# SCH_PCBProjectCard_2024-06-02.net
KiCad netlist of a schematic drawn in EasyEDA
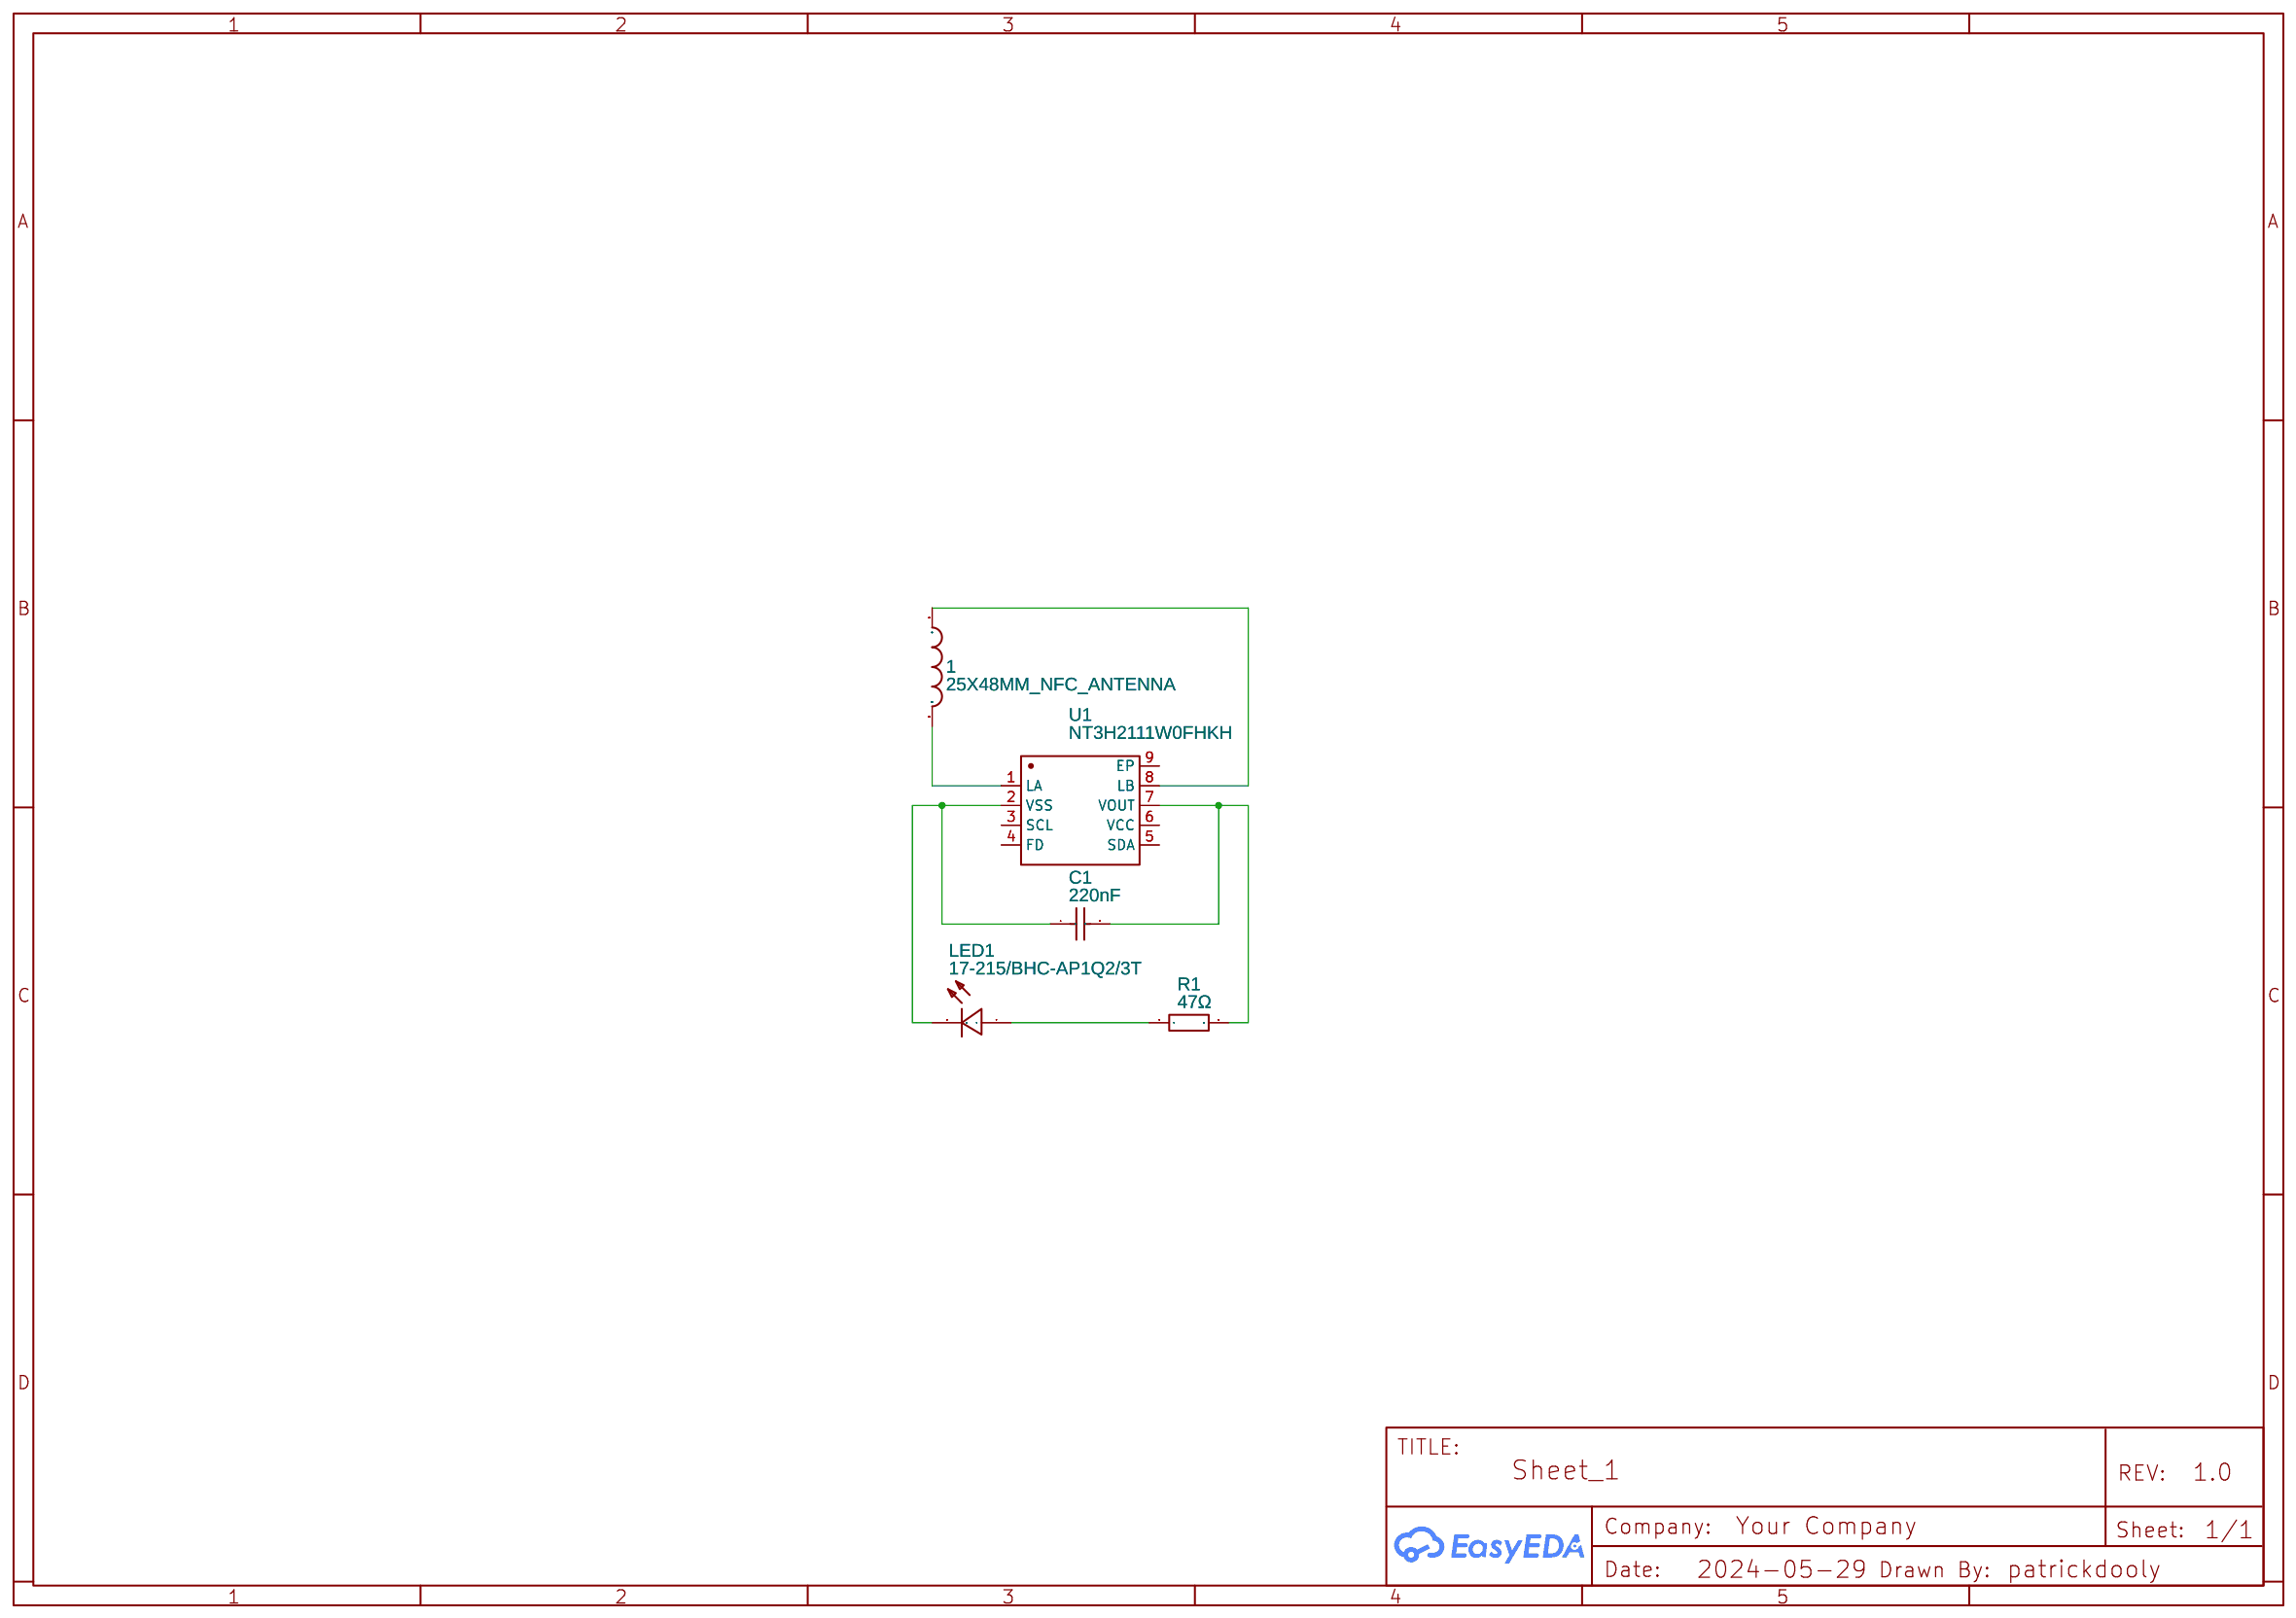
[diagram p0: schematic sheet]

(export (version "E")
  (design (tool "Eeschema 10.0.6"))
  (components
    (comp (ref "1") (value "25X48MM_NFC_ANTENNA") (libsource (lib "") (part "25X48MM_NFC_ANTENNA")))
    (comp (ref "C1")
      (value "220nF")
      (fields
        (field (name "Manufacturer Part") "CL10B224KA8NNNC")
        (field (name "Manufacturer") "SAMSUNG(三星)")
      )
      (libsource (lib "") (part "CL10B224KA8NNNC"))
    )
    (comp (ref "LED1")
      (value "17-215/BHC-AP1Q2/3T")
      (fields (field (name "Manufacturer") "EVERLIGHT(亿光)"))
      (libsource (lib "") (part "17-215/BHC-AP1Q2/3T"))
    )
    (comp (ref "R1")
      (value "47Ω")
      (fields
        (field (name "Manufacturer Part") "0603WAF470JT5E")
        (field (name "Manufacturer") "UNI-ROYAL(厚声)")
      )
      (libsource (lib "") (part "0603WAF470JT5E"))
    )
    (comp (ref "U1")
      (value "NT3H2111W0FHKH")
      (fields (field (name "Manufacturer") "NXP(恩智浦)"))
      (libsource (lib "") (part "NT3H2111W0FHKH"))
    )
  )
  (nets
    (net (code "1") (name "Net-(LED1-Pad1)") (class "Default")
      (node (ref "LED1") (pin "1") (pinfunction "1_1") (pintype "unspecified"))
      (node (ref "R1") (pin "1") (pinfunction "1_1") (pintype "input"))
    )
    (net (code "2") (name "Net-(U1-LA)") (class "Default")
      (node (ref "1") (pin "P$2") (pinfunction "P$2_P$2") (pintype "bidirectional"))
      (node (ref "U1") (pin "1") (pinfunction "LA_1") (pintype "unspecified"))
    )
    (net (code "3") (name "Net-(U1-LB)") (class "Default")
      (node (ref "1") (pin "P$1") (pinfunction "P$1_P$1") (pintype "bidirectional"))
      (node (ref "U1") (pin "8") (pinfunction "LB_8") (pintype "unspecified"))
    )
    (net (code "4") (name "Net-(U1-VOUT)") (class "Default")
      (node (ref "C1") (pin "2") (pinfunction "2_2") (pintype "input"))
      (node (ref "R1") (pin "2") (pinfunction "2_2") (pintype "input"))
      (node (ref "U1") (pin "7") (pinfunction "VOUT_7") (pintype "unspecified"))
    )
    (net (code "5") (name "Net-(U1-VSS)") (class "Default")
      (node (ref "C1") (pin "1") (pinfunction "1_1") (pintype "input"))
      (node (ref "LED1") (pin "2") (pinfunction "2_2") (pintype "unspecified"))
      (node (ref "U1") (pin "2") (pinfunction "VSS_2") (pintype "unspecified"))
    )
    (net (code "6") (name "unconnected-(U1-EP-Pad9)") (class "Default")
      (node (ref "U1") (pin "9") (pinfunction "EP_9") (pintype "unspecified"))
    )
    (net (code "7") (name "unconnected-(U1-FD-Pad4)") (class "Default")
      (node (ref "U1") (pin "4") (pinfunction "FD_4") (pintype "unspecified"))
    )
    (net (code "8") (name "unconnected-(U1-SCL-Pad3)") (class "Default")
      (node (ref "U1") (pin "3") (pinfunction "SCL_3") (pintype "unspecified"))
    )
    (net (code "9") (name "unconnected-(U1-SDA-Pad5)") (class "Default")
      (node (ref "U1") (pin "5") (pinfunction "SDA_5") (pintype "unspecified"))
    )
    (net (code "10") (name "unconnected-(U1-VCC-Pad6)") (class "Default")
      (node (ref "U1") (pin "6") (pinfunction "VCC_6") (pintype "unspecified"))
    )
  )
)
